# Si7021.net
KiCad netlist of a schematic drawn in Altium Designer
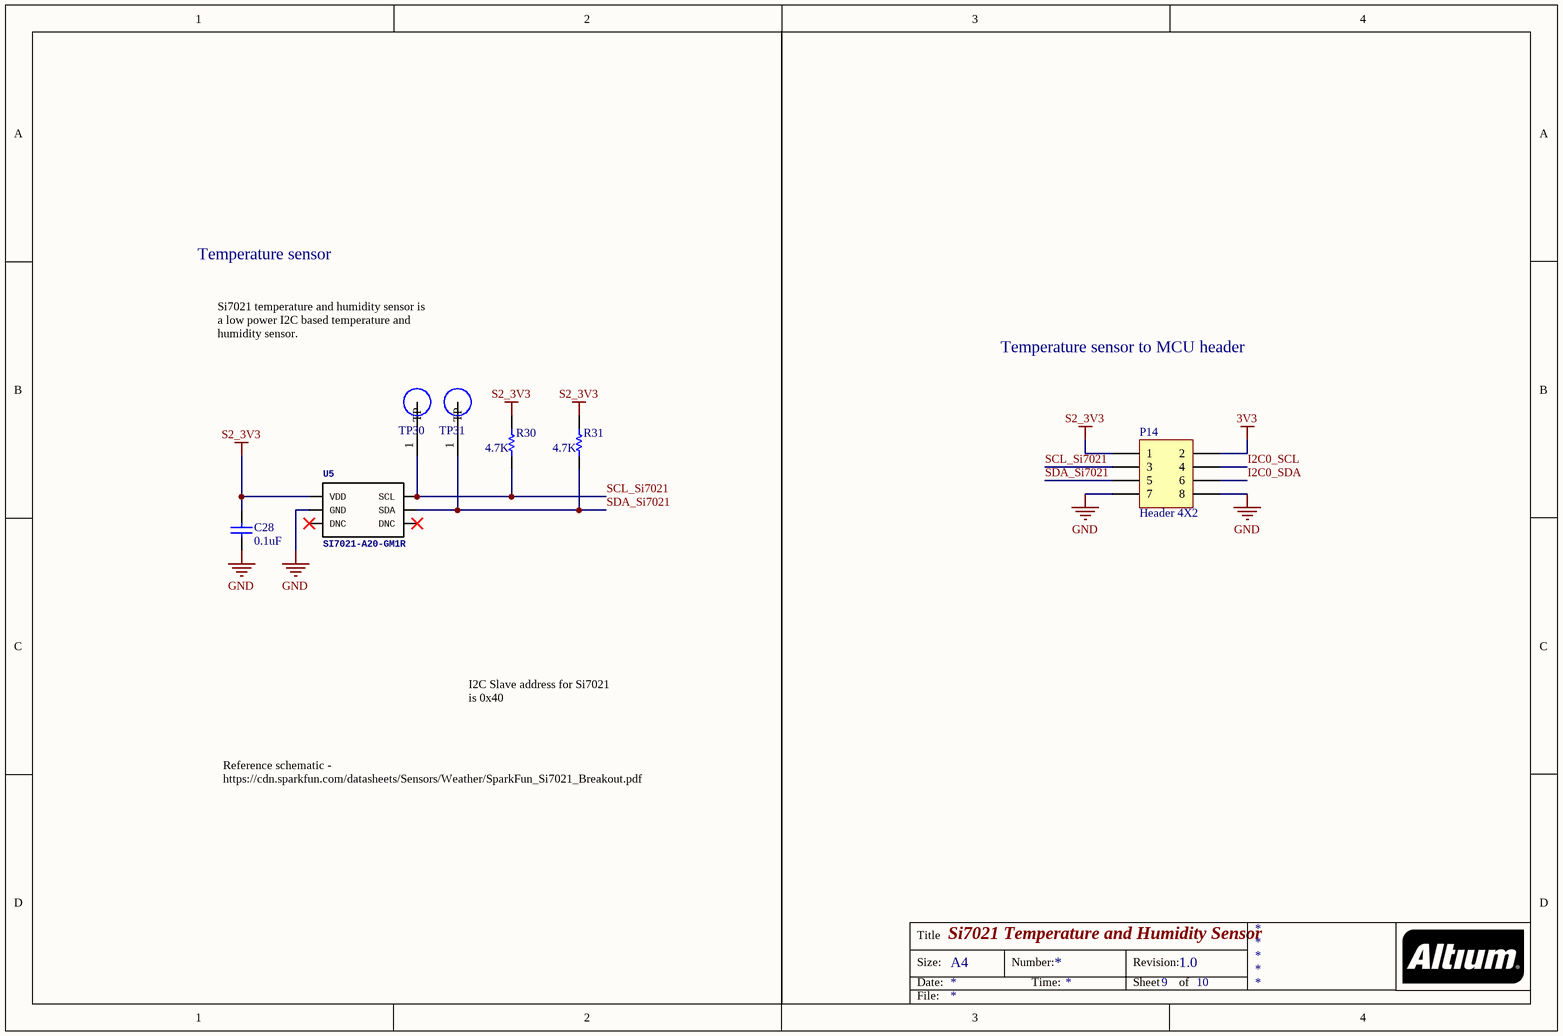
[diagram p0: Si7021.SchDoc]

(export (version "E")
  (design (tool "Eeschema 10.0.6"))
  (components
    (comp (ref "C28")
      (value "0.1uF")
      (footprint "1608[0603]")
      (description "Capacitor")
      (fields
        (field (name "DIGI-KEY PART NUMBER") "1276-1005-1-ND")
        (field (name "MANUFACTURER") "Samsung Electro-Mechanics")
      )
      (libsource (lib "Miscellaneous Devices") (part "Cap"))
    )
    (comp (ref "P14")
      (value "Header 4X2")
      (footprint "4-PIN")
      (description "Header, 4-Pin, Dual row")
      (fields
        (field (name "DIGI-KEY PART NUMBER") "A121467-ND")
        (field (name "MANUFACTURER") "TE Connectivity")
      )
      (libsource (lib "Miscellaneous Connectors") (part "Header 4X2"))
    )
    (comp (ref "R30")
      (value "4.7K")
      (footprint "1608[0603]")
      (description "RES SMD 4.7K OHM 5% 1/10W 0603")
      (fields (field (name "DIGI-KEY PART NUMBER") "311-4.7KGRCT-ND") (field (name "MANUFACTURER") "Yageo"))
      (libsource (lib "Miscellaneous Devices") (part "Res1"))
    )
    (comp (ref "R31")
      (value "4.7K")
      (footprint "1608[0603]")
      (description "RES SMD 4.7K OHM 5% 1/10W 0603")
      (fields (field (name "DIGI-KEY PART NUMBER") "311-4.7KGRCT-ND") (field (name "MANUFACTURER") "Yageo"))
      (libsource (lib "Miscellaneous Devices") (part "Res1"))
    )
    (comp (ref "TP30")
      (value "TP")
      (footprint "TP")
      (description "PC TEST POINT MINIATURE")
      (fields
        (field (name "MANUFACTURER") "Keystone Electronics")
        (field (name "DIGI-KEY PART NUMBER") "36-5019CT-ND")
      )
      (libsource (lib "TP") (part "TP"))
    )
    (comp (ref "TP31")
      (value "TP")
      (footprint "TP")
      (description "PC TEST POINT MINIATURE")
      (fields
        (field (name "MANUFACTURER") "Keystone Electronics")
        (field (name "DIGI-KEY PART NUMBER") "36-5019CT-ND")
      )
      (libsource (lib "TP") (part "TP"))
    )
    (comp (ref "U5")
      (value "SI7021-A20-GM1R")
      (footprint "SI7021")
      (description "SENS HUMID/TEMP 3.6V I2C 2% 6DFN")
      (fields
        (field (name "DIGI-KEY PART NUMBER") "336-4380-1-ND")
        (field (name "MANUFACTURER") "Silicon Labs")
      )
      (libsource (lib "Hydrated_Buffs") (part "SI7021"))
    )
  )
  (nets
    (net (code "1") (name "/I2C0_SCL") (class "Default")
      (node (ref "P14") (pin "4") (pinfunction "4_4") (pintype "passive"))
    )
    (net (code "2") (name "/I2C0_SDA") (class "Default")
      (node (ref "P14") (pin "6") (pinfunction "6_6") (pintype "passive"))
    )
    (net (code "3") (name "/SCL_Si7021") (class "Default")
      (node (ref "P14") (pin "3") (pinfunction "3_3") (pintype "passive"))
      (node (ref "R30") (pin "1") (pinfunction "1_1") (pintype "passive"))
      (node (ref "TP30") (pin "1") (pinfunction "TP_1") (pintype "passive"))
      (node (ref "U5") (pin "SCL") (pinfunction "SCL_SCL") (pintype "passive"))
    )
    (net (code "4") (name "/SDA_Si7021") (class "Default")
      (node (ref "P14") (pin "5") (pinfunction "5_5") (pintype "passive"))
      (node (ref "R31") (pin "1") (pinfunction "1_1") (pintype "passive"))
      (node (ref "TP31") (pin "1") (pinfunction "TP_1") (pintype "passive"))
      (node (ref "U5") (pin "SDA") (pinfunction "SDA_SDA") (pintype "passive"))
    )
    (net (code "5") (name "3V3") (class "Default")
      (node (ref "P14") (pin "2") (pinfunction "2_2") (pintype "passive"))
    )
    (net (code "6") (name "GND") (class "Default")
      (node (ref "C28") (pin "1") (pinfunction "1_1") (pintype "passive"))
      (node (ref "P14") (pin "7") (pinfunction "7_7") (pintype "passive"))
      (node (ref "P14") (pin "8") (pinfunction "8_8") (pintype "passive"))
      (node (ref "U5") (pin "GND") (pinfunction "GND_GND") (pintype "power_in"))
    )
    (net (code "7") (name "S2_3V3") (class "Default")
      (node (ref "C28") (pin "2") (pinfunction "2_2") (pintype "passive"))
      (node (ref "P14") (pin "1") (pinfunction "1_1") (pintype "passive"))
      (node (ref "R30") (pin "2") (pinfunction "2_2") (pintype "passive"))
      (node (ref "R31") (pin "2") (pinfunction "2_2") (pintype "passive"))
      (node (ref "U5") (pin "VDD") (pinfunction "VDD_VDD") (pintype "power_in"))
    )
    (net (code "8") (name "unconnected-(U5-DNC-PadNC@3)") (class "Default")
      (node (ref "U5") (pin "NC@3") (pinfunction "DNC_NC@3") (pintype "power_in+no_connect"))
    )
    (net (code "9") (name "unconnected-(U5-DNC-PadNC@4)") (class "Default")
      (node (ref "U5") (pin "NC@4") (pinfunction "DNC_NC@4") (pintype "passive+no_connect"))
    )
  )
)
